# schematic.net
KiCad netlist of a schematic drawn in Altium Designer
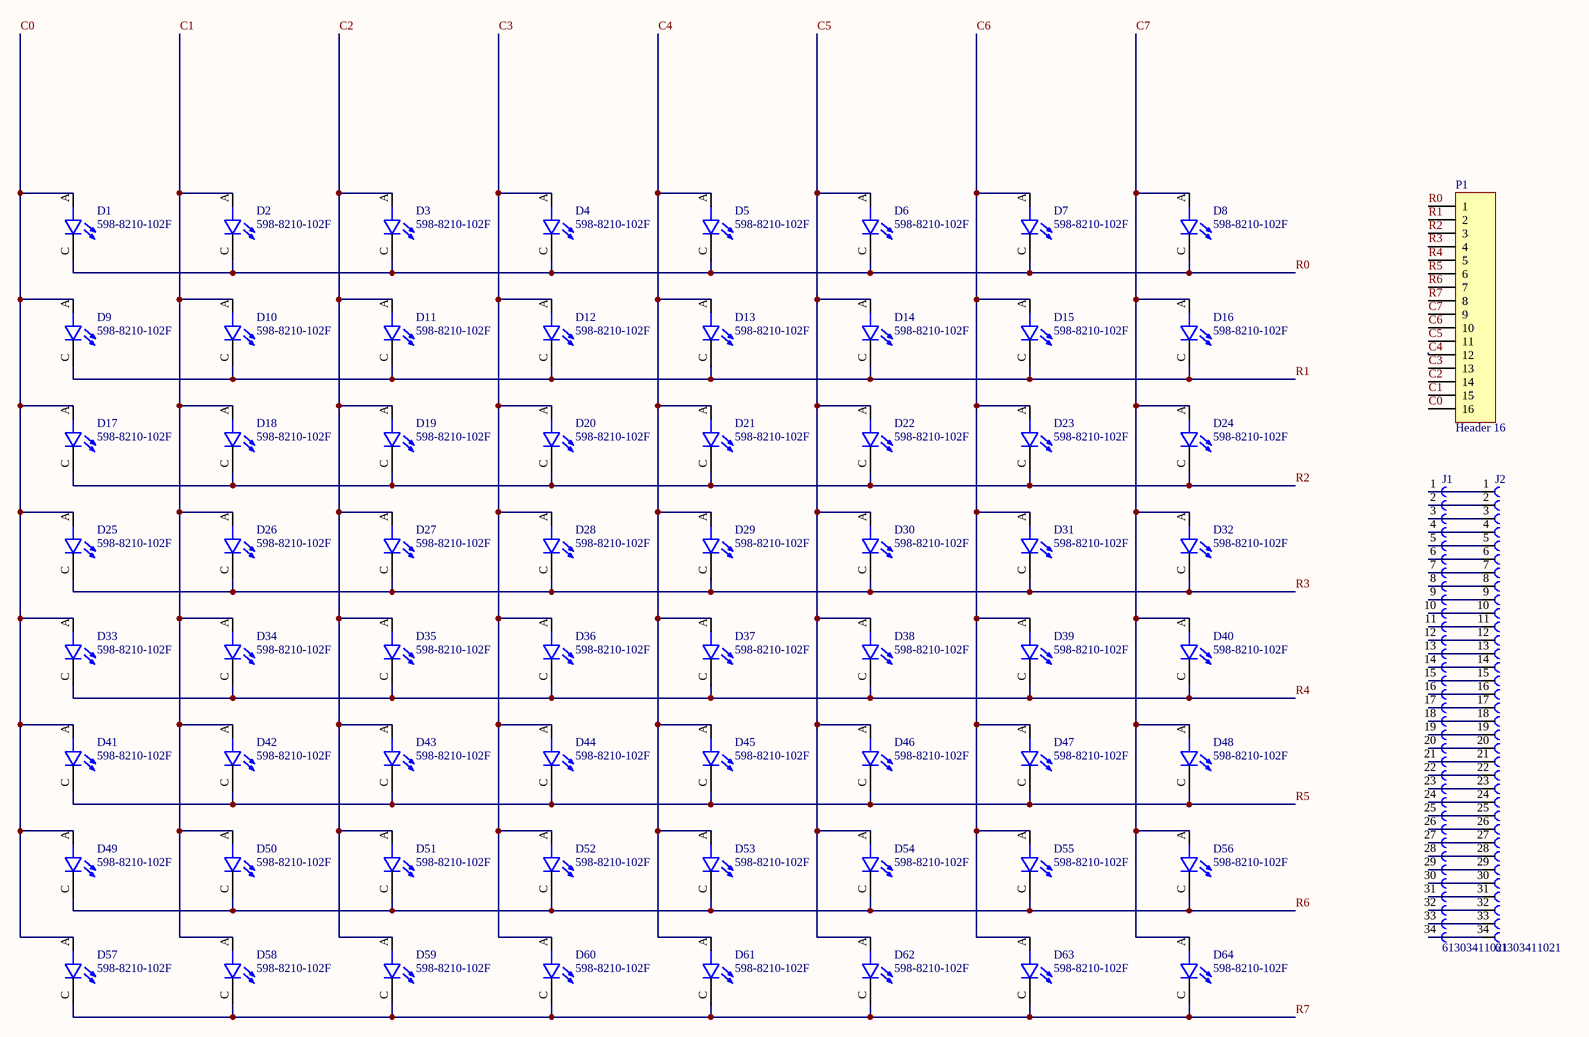
[diagram p0: schematic.SchDoc]

(export (version "E")
  (design (tool "Eeschema 10.0.6"))
  (components
    (comp (ref "D1")
      (value "598-8210-102F")
      (footprint "LEDSC160X320X90-2N")
      (description "Red 635nm LED Indication - Discrete 2V 1206 (3216 Metric)")
      (fields (field (name "MF") "{'manufacturer': u'Dialight'}"))
      (libsource (lib "SnapEDA_Library") (part "598-8210-102F"))
    )
    (comp (ref "D2")
      (value "598-8210-102F")
      (footprint "LEDSC160X320X90-2N")
      (description "Red 635nm LED Indication - Discrete 2V 1206 (3216 Metric)")
      (fields (field (name "MF") "{'manufacturer': u'Dialight'}"))
      (libsource (lib "SnapEDA_Library") (part "598-8210-102F"))
    )
    (comp (ref "D3")
      (value "598-8210-102F")
      (footprint "LEDSC160X320X90-2N")
      (description "Red 635nm LED Indication - Discrete 2V 1206 (3216 Metric)")
      (fields (field (name "MF") "{'manufacturer': u'Dialight'}"))
      (libsource (lib "SnapEDA_Library") (part "598-8210-102F"))
    )
    (comp (ref "D4")
      (value "598-8210-102F")
      (footprint "LEDSC160X320X90-2N")
      (description "Red 635nm LED Indication - Discrete 2V 1206 (3216 Metric)")
      (fields (field (name "MF") "{'manufacturer': u'Dialight'}"))
      (libsource (lib "SnapEDA_Library") (part "598-8210-102F"))
    )
    (comp (ref "D5")
      (value "598-8210-102F")
      (footprint "LEDSC160X320X90-2N")
      (description "Red 635nm LED Indication - Discrete 2V 1206 (3216 Metric)")
      (fields (field (name "MF") "{'manufacturer': u'Dialight'}"))
      (libsource (lib "SnapEDA_Library") (part "598-8210-102F"))
    )
    (comp (ref "D6")
      (value "598-8210-102F")
      (footprint "LEDSC160X320X90-2N")
      (description "Red 635nm LED Indication - Discrete 2V 1206 (3216 Metric)")
      (fields (field (name "MF") "{'manufacturer': u'Dialight'}"))
      (libsource (lib "SnapEDA_Library") (part "598-8210-102F"))
    )
    (comp (ref "D7")
      (value "598-8210-102F")
      (footprint "LEDSC160X320X90-2N")
      (description "Red 635nm LED Indication - Discrete 2V 1206 (3216 Metric)")
      (fields (field (name "MF") "{'manufacturer': u'Dialight'}"))
      (libsource (lib "SnapEDA_Library") (part "598-8210-102F"))
    )
    (comp (ref "D8")
      (value "598-8210-102F")
      (footprint "LEDSC160X320X90-2N")
      (description "Red 635nm LED Indication - Discrete 2V 1206 (3216 Metric)")
      (fields (field (name "MF") "{'manufacturer': u'Dialight'}"))
      (libsource (lib "SnapEDA_Library") (part "598-8210-102F"))
    )
    (comp (ref "D9")
      (value "598-8210-102F")
      (footprint "LEDSC160X320X90-2N")
      (description "Red 635nm LED Indication - Discrete 2V 1206 (3216 Metric)")
      (fields (field (name "MF") "{'manufacturer': u'Dialight'}"))
      (libsource (lib "SnapEDA_Library") (part "598-8210-102F"))
    )
    (comp (ref "D10")
      (value "598-8210-102F")
      (footprint "LEDSC160X320X90-2N")
      (description "Red 635nm LED Indication - Discrete 2V 1206 (3216 Metric)")
      (fields (field (name "MF") "{'manufacturer': u'Dialight'}"))
      (libsource (lib "SnapEDA_Library") (part "598-8210-102F"))
    )
    (comp (ref "D11")
      (value "598-8210-102F")
      (footprint "LEDSC160X320X90-2N")
      (description "Red 635nm LED Indication - Discrete 2V 1206 (3216 Metric)")
      (fields (field (name "MF") "{'manufacturer': u'Dialight'}"))
      (libsource (lib "SnapEDA_Library") (part "598-8210-102F"))
    )
    (comp (ref "D12")
      (value "598-8210-102F")
      (footprint "LEDSC160X320X90-2N")
      (description "Red 635nm LED Indication - Discrete 2V 1206 (3216 Metric)")
      (fields (field (name "MF") "{'manufacturer': u'Dialight'}"))
      (libsource (lib "SnapEDA_Library") (part "598-8210-102F"))
    )
    (comp (ref "D13")
      (value "598-8210-102F")
      (footprint "LEDSC160X320X90-2N")
      (description "Red 635nm LED Indication - Discrete 2V 1206 (3216 Metric)")
      (fields (field (name "MF") "{'manufacturer': u'Dialight'}"))
      (libsource (lib "SnapEDA_Library") (part "598-8210-102F"))
    )
    (comp (ref "D14")
      (value "598-8210-102F")
      (footprint "LEDSC160X320X90-2N")
      (description "Red 635nm LED Indication - Discrete 2V 1206 (3216 Metric)")
      (fields (field (name "MF") "{'manufacturer': u'Dialight'}"))
      (libsource (lib "SnapEDA_Library") (part "598-8210-102F"))
    )
    (comp (ref "D15")
      (value "598-8210-102F")
      (footprint "LEDSC160X320X90-2N")
      (description "Red 635nm LED Indication - Discrete 2V 1206 (3216 Metric)")
      (fields (field (name "MF") "{'manufacturer': u'Dialight'}"))
      (libsource (lib "SnapEDA_Library") (part "598-8210-102F"))
    )
    (comp (ref "D16")
      (value "598-8210-102F")
      (footprint "LEDSC160X320X90-2N")
      (description "Red 635nm LED Indication - Discrete 2V 1206 (3216 Metric)")
      (fields (field (name "MF") "{'manufacturer': u'Dialight'}"))
      (libsource (lib "SnapEDA_Library") (part "598-8210-102F"))
    )
    (comp (ref "D17")
      (value "598-8210-102F")
      (footprint "LEDSC160X320X90-2N")
      (description "Red 635nm LED Indication - Discrete 2V 1206 (3216 Metric)")
      (fields (field (name "MF") "{'manufacturer': u'Dialight'}"))
      (libsource (lib "SnapEDA_Library") (part "598-8210-102F"))
    )
    (comp (ref "D18")
      (value "598-8210-102F")
      (footprint "LEDSC160X320X90-2N")
      (description "Red 635nm LED Indication - Discrete 2V 1206 (3216 Metric)")
      (fields (field (name "MF") "{'manufacturer': u'Dialight'}"))
      (libsource (lib "SnapEDA_Library") (part "598-8210-102F"))
    )
    (comp (ref "D19")
      (value "598-8210-102F")
      (footprint "LEDSC160X320X90-2N")
      (description "Red 635nm LED Indication - Discrete 2V 1206 (3216 Metric)")
      (fields (field (name "MF") "{'manufacturer': u'Dialight'}"))
      (libsource (lib "SnapEDA_Library") (part "598-8210-102F"))
    )
    (comp (ref "D20")
      (value "598-8210-102F")
      (footprint "LEDSC160X320X90-2N")
      (description "Red 635nm LED Indication - Discrete 2V 1206 (3216 Metric)")
      (fields (field (name "MF") "{'manufacturer': u'Dialight'}"))
      (libsource (lib "SnapEDA_Library") (part "598-8210-102F"))
    )
    (comp (ref "D21")
      (value "598-8210-102F")
      (footprint "LEDSC160X320X90-2N")
      (description "Red 635nm LED Indication - Discrete 2V 1206 (3216 Metric)")
      (fields (field (name "MF") "{'manufacturer': u'Dialight'}"))
      (libsource (lib "SnapEDA_Library") (part "598-8210-102F"))
    )
    (comp (ref "D22")
      (value "598-8210-102F")
      (footprint "LEDSC160X320X90-2N")
      (description "Red 635nm LED Indication - Discrete 2V 1206 (3216 Metric)")
      (fields (field (name "MF") "{'manufacturer': u'Dialight'}"))
      (libsource (lib "SnapEDA_Library") (part "598-8210-102F"))
    )
    (comp (ref "D23")
      (value "598-8210-102F")
      (footprint "LEDSC160X320X90-2N")
      (description "Red 635nm LED Indication - Discrete 2V 1206 (3216 Metric)")
      (fields (field (name "MF") "{'manufacturer': u'Dialight'}"))
      (libsource (lib "SnapEDA_Library") (part "598-8210-102F"))
    )
    (comp (ref "D24")
      (value "598-8210-102F")
      (footprint "LEDSC160X320X90-2N")
      (description "Red 635nm LED Indication - Discrete 2V 1206 (3216 Metric)")
      (fields (field (name "MF") "{'manufacturer': u'Dialight'}"))
      (libsource (lib "SnapEDA_Library") (part "598-8210-102F"))
    )
    (comp (ref "D25")
      (value "598-8210-102F")
      (footprint "LEDSC160X320X90-2N")
      (description "Red 635nm LED Indication - Discrete 2V 1206 (3216 Metric)")
      (fields (field (name "MF") "{'manufacturer': u'Dialight'}"))
      (libsource (lib "SnapEDA_Library") (part "598-8210-102F"))
    )
    (comp (ref "D26")
      (value "598-8210-102F")
      (footprint "LEDSC160X320X90-2N")
      (description "Red 635nm LED Indication - Discrete 2V 1206 (3216 Metric)")
      (fields (field (name "MF") "{'manufacturer': u'Dialight'}"))
      (libsource (lib "SnapEDA_Library") (part "598-8210-102F"))
    )
    (comp (ref "D27")
      (value "598-8210-102F")
      (footprint "LEDSC160X320X90-2N")
      (description "Red 635nm LED Indication - Discrete 2V 1206 (3216 Metric)")
      (fields (field (name "MF") "{'manufacturer': u'Dialight'}"))
      (libsource (lib "SnapEDA_Library") (part "598-8210-102F"))
    )
    (comp (ref "D28")
      (value "598-8210-102F")
      (footprint "LEDSC160X320X90-2N")
      (description "Red 635nm LED Indication - Discrete 2V 1206 (3216 Metric)")
      (fields (field (name "MF") "{'manufacturer': u'Dialight'}"))
      (libsource (lib "SnapEDA_Library") (part "598-8210-102F"))
    )
    (comp (ref "D29")
      (value "598-8210-102F")
      (footprint "LEDSC160X320X90-2N")
      (description "Red 635nm LED Indication - Discrete 2V 1206 (3216 Metric)")
      (fields (field (name "MF") "{'manufacturer': u'Dialight'}"))
      (libsource (lib "SnapEDA_Library") (part "598-8210-102F"))
    )
    (comp (ref "D30")
      (value "598-8210-102F")
      (footprint "LEDSC160X320X90-2N")
      (description "Red 635nm LED Indication - Discrete 2V 1206 (3216 Metric)")
      (fields (field (name "MF") "{'manufacturer': u'Dialight'}"))
      (libsource (lib "SnapEDA_Library") (part "598-8210-102F"))
    )
    (comp (ref "D31")
      (value "598-8210-102F")
      (footprint "LEDSC160X320X90-2N")
      (description "Red 635nm LED Indication - Discrete 2V 1206 (3216 Metric)")
      (fields (field (name "MF") "{'manufacturer': u'Dialight'}"))
      (libsource (lib "SnapEDA_Library") (part "598-8210-102F"))
    )
    (comp (ref "D32")
      (value "598-8210-102F")
      (footprint "LEDSC160X320X90-2N")
      (description "Red 635nm LED Indication - Discrete 2V 1206 (3216 Metric)")
      (fields (field (name "MF") "{'manufacturer': u'Dialight'}"))
      (libsource (lib "SnapEDA_Library") (part "598-8210-102F"))
    )
    (comp (ref "D33")
      (value "598-8210-102F")
      (footprint "LEDSC160X320X90-2N")
      (description "Red 635nm LED Indication - Discrete 2V 1206 (3216 Metric)")
      (fields (field (name "MF") "{'manufacturer': u'Dialight'}"))
      (libsource (lib "SnapEDA_Library") (part "598-8210-102F"))
    )
    (comp (ref "D34")
      (value "598-8210-102F")
      (footprint "LEDSC160X320X90-2N")
      (description "Red 635nm LED Indication - Discrete 2V 1206 (3216 Metric)")
      (fields (field (name "MF") "{'manufacturer': u'Dialight'}"))
      (libsource (lib "SnapEDA_Library") (part "598-8210-102F"))
    )
    (comp (ref "D35")
      (value "598-8210-102F")
      (footprint "LEDSC160X320X90-2N")
      (description "Red 635nm LED Indication - Discrete 2V 1206 (3216 Metric)")
      (fields (field (name "MF") "{'manufacturer': u'Dialight'}"))
      (libsource (lib "SnapEDA_Library") (part "598-8210-102F"))
    )
    (comp (ref "D36")
      (value "598-8210-102F")
      (footprint "LEDSC160X320X90-2N")
      (description "Red 635nm LED Indication - Discrete 2V 1206 (3216 Metric)")
      (fields (field (name "MF") "{'manufacturer': u'Dialight'}"))
      (libsource (lib "SnapEDA_Library") (part "598-8210-102F"))
    )
    (comp (ref "D37")
      (value "598-8210-102F")
      (footprint "LEDSC160X320X90-2N")
      (description "Red 635nm LED Indication - Discrete 2V 1206 (3216 Metric)")
      (fields (field (name "MF") "{'manufacturer': u'Dialight'}"))
      (libsource (lib "SnapEDA_Library") (part "598-8210-102F"))
    )
    (comp (ref "D38")
      (value "598-8210-102F")
      (footprint "LEDSC160X320X90-2N")
      (description "Red 635nm LED Indication - Discrete 2V 1206 (3216 Metric)")
      (fields (field (name "MF") "{'manufacturer': u'Dialight'}"))
      (libsource (lib "SnapEDA_Library") (part "598-8210-102F"))
    )
    (comp (ref "D39")
      (value "598-8210-102F")
      (footprint "LEDSC160X320X90-2N")
      (description "Red 635nm LED Indication - Discrete 2V 1206 (3216 Metric)")
      (fields (field (name "MF") "{'manufacturer': u'Dialight'}"))
      (libsource (lib "SnapEDA_Library") (part "598-8210-102F"))
    )
    (comp (ref "D40")
      (value "598-8210-102F")
      (footprint "LEDSC160X320X90-2N")
      (description "Red 635nm LED Indication - Discrete 2V 1206 (3216 Metric)")
      (fields (field (name "MF") "{'manufacturer': u'Dialight'}"))
      (libsource (lib "SnapEDA_Library") (part "598-8210-102F"))
    )
    (comp (ref "D41")
      (value "598-8210-102F")
      (footprint "LEDSC160X320X90-2N")
      (description "Red 635nm LED Indication - Discrete 2V 1206 (3216 Metric)")
      (fields (field (name "MF") "{'manufacturer': u'Dialight'}"))
      (libsource (lib "SnapEDA_Library") (part "598-8210-102F"))
    )
    (comp (ref "D42")
      (value "598-8210-102F")
      (footprint "LEDSC160X320X90-2N")
      (description "Red 635nm LED Indication - Discrete 2V 1206 (3216 Metric)")
      (fields (field (name "MF") "{'manufacturer': u'Dialight'}"))
      (libsource (lib "SnapEDA_Library") (part "598-8210-102F"))
    )
    (comp (ref "D43")
      (value "598-8210-102F")
      (footprint "LEDSC160X320X90-2N")
      (description "Red 635nm LED Indication - Discrete 2V 1206 (3216 Metric)")
      (fields (field (name "MF") "{'manufacturer': u'Dialight'}"))
      (libsource (lib "SnapEDA_Library") (part "598-8210-102F"))
    )
    (comp (ref "D44")
      (value "598-8210-102F")
      (footprint "LEDSC160X320X90-2N")
      (description "Red 635nm LED Indication - Discrete 2V 1206 (3216 Metric)")
      (fields (field (name "MF") "{'manufacturer': u'Dialight'}"))
      (libsource (lib "SnapEDA_Library") (part "598-8210-102F"))
    )
    (comp (ref "D45")
      (value "598-8210-102F")
      (footprint "LEDSC160X320X90-2N")
      (description "Red 635nm LED Indication - Discrete 2V 1206 (3216 Metric)")
      (fields (field (name "MF") "{'manufacturer': u'Dialight'}"))
      (libsource (lib "SnapEDA_Library") (part "598-8210-102F"))
    )
    (comp (ref "D46")
      (value "598-8210-102F")
      (footprint "LEDSC160X320X90-2N")
      (description "Red 635nm LED Indication - Discrete 2V 1206 (3216 Metric)")
      (fields (field (name "MF") "{'manufacturer': u'Dialight'}"))
      (libsource (lib "SnapEDA_Library") (part "598-8210-102F"))
    )
    (comp (ref "D47")
      (value "598-8210-102F")
      (footprint "LEDSC160X320X90-2N")
      (description "Red 635nm LED Indication - Discrete 2V 1206 (3216 Metric)")
      (fields (field (name "MF") "{'manufacturer': u'Dialight'}"))
      (libsource (lib "SnapEDA_Library") (part "598-8210-102F"))
    )
    (comp (ref "D48")
      (value "598-8210-102F")
      (footprint "LEDSC160X320X90-2N")
      (description "Red 635nm LED Indication - Discrete 2V 1206 (3216 Metric)")
      (fields (field (name "MF") "{'manufacturer': u'Dialight'}"))
      (libsource (lib "SnapEDA_Library") (part "598-8210-102F"))
    )
    (comp (ref "D49")
      (value "598-8210-102F")
      (footprint "LEDSC160X320X90-2N")
      (description "Red 635nm LED Indication - Discrete 2V 1206 (3216 Metric)")
      (fields (field (name "MF") "{'manufacturer': u'Dialight'}"))
      (libsource (lib "SnapEDA_Library") (part "598-8210-102F"))
    )
    (comp (ref "D50")
      (value "598-8210-102F")
      (footprint "LEDSC160X320X90-2N")
      (description "Red 635nm LED Indication - Discrete 2V 1206 (3216 Metric)")
      (fields (field (name "MF") "{'manufacturer': u'Dialight'}"))
      (libsource (lib "SnapEDA_Library") (part "598-8210-102F"))
    )
    (comp (ref "D51")
      (value "598-8210-102F")
      (footprint "LEDSC160X320X90-2N")
      (description "Red 635nm LED Indication - Discrete 2V 1206 (3216 Metric)")
      (fields (field (name "MF") "{'manufacturer': u'Dialight'}"))
      (libsource (lib "SnapEDA_Library") (part "598-8210-102F"))
    )
    (comp (ref "D52")
      (value "598-8210-102F")
      (footprint "LEDSC160X320X90-2N")
      (description "Red 635nm LED Indication - Discrete 2V 1206 (3216 Metric)")
      (fields (field (name "MF") "{'manufacturer': u'Dialight'}"))
      (libsource (lib "SnapEDA_Library") (part "598-8210-102F"))
    )
    (comp (ref "D53")
      (value "598-8210-102F")
      (footprint "LEDSC160X320X90-2N")
      (description "Red 635nm LED Indication - Discrete 2V 1206 (3216 Metric)")
      (fields (field (name "MF") "{'manufacturer': u'Dialight'}"))
      (libsource (lib "SnapEDA_Library") (part "598-8210-102F"))
    )
    (comp (ref "D54")
      (value "598-8210-102F")
      (footprint "LEDSC160X320X90-2N")
      (description "Red 635nm LED Indication - Discrete 2V 1206 (3216 Metric)")
      (fields (field (name "MF") "{'manufacturer': u'Dialight'}"))
      (libsource (lib "SnapEDA_Library") (part "598-8210-102F"))
    )
    (comp (ref "D55")
      (value "598-8210-102F")
      (footprint "LEDSC160X320X90-2N")
      (description "Red 635nm LED Indication - Discrete 2V 1206 (3216 Metric)")
      (fields (field (name "MF") "{'manufacturer': u'Dialight'}"))
      (libsource (lib "SnapEDA_Library") (part "598-8210-102F"))
    )
    (comp (ref "D56")
      (value "598-8210-102F")
      (footprint "LEDSC160X320X90-2N")
      (description "Red 635nm LED Indication - Discrete 2V 1206 (3216 Metric)")
      (fields (field (name "MF") "{'manufacturer': u'Dialight'}"))
      (libsource (lib "SnapEDA_Library") (part "598-8210-102F"))
    )
    (comp (ref "D57")
      (value "598-8210-102F")
      (footprint "LEDSC160X320X90-2N")
      (description "Red 635nm LED Indication - Discrete 2V 1206 (3216 Metric)")
      (fields (field (name "MF") "{'manufacturer': u'Dialight'}"))
      (libsource (lib "SnapEDA_Library") (part "598-8210-102F"))
    )
    (comp (ref "D58")
      (value "598-8210-102F")
      (footprint "LEDSC160X320X90-2N")
      (description "Red 635nm LED Indication - Discrete 2V 1206 (3216 Metric)")
      (fields (field (name "MF") "{'manufacturer': u'Dialight'}"))
      (libsource (lib "SnapEDA_Library") (part "598-8210-102F"))
    )
    (comp (ref "D59")
      (value "598-8210-102F")
      (footprint "LEDSC160X320X90-2N")
      (description "Red 635nm LED Indication - Discrete 2V 1206 (3216 Metric)")
      (fields (field (name "MF") "{'manufacturer': u'Dialight'}"))
      (libsource (lib "SnapEDA_Library") (part "598-8210-102F"))
    )
    (comp (ref "D60")
      (value "598-8210-102F")
      (footprint "LEDSC160X320X90-2N")
      (description "Red 635nm LED Indication - Discrete 2V 1206 (3216 Metric)")
      (fields (field (name "MF") "{'manufacturer': u'Dialight'}"))
      (libsource (lib "SnapEDA_Library") (part "598-8210-102F"))
    )
    (comp (ref "D61")
      (value "598-8210-102F")
      (footprint "LEDSC160X320X90-2N")
      (description "Red 635nm LED Indication - Discrete 2V 1206 (3216 Metric)")
      (fields (field (name "MF") "{'manufacturer': u'Dialight'}"))
      (libsource (lib "SnapEDA_Library") (part "598-8210-102F"))
    )
    (comp (ref "D62")
      (value "598-8210-102F")
      (footprint "LEDSC160X320X90-2N")
      (description "Red 635nm LED Indication - Discrete 2V 1206 (3216 Metric)")
      (fields (field (name "MF") "{'manufacturer': u'Dialight'}"))
      (libsource (lib "SnapEDA_Library") (part "598-8210-102F"))
    )
    (comp (ref "D63")
      (value "598-8210-102F")
      (footprint "LEDSC160X320X90-2N")
      (description "Red 635nm LED Indication - Discrete 2V 1206 (3216 Metric)")
      (fields (field (name "MF") "{'manufacturer': u'Dialight'}"))
      (libsource (lib "SnapEDA_Library") (part "598-8210-102F"))
    )
    (comp (ref "D64")
      (value "598-8210-102F")
      (footprint "LEDSC160X320X90-2N")
      (description "Red 635nm LED Indication - Discrete 2V 1206 (3216 Metric)")
      (fields (field (name "MF") "{'manufacturer': u'Dialight'}"))
      (libsource (lib "SnapEDA_Library") (part "598-8210-102F"))
    )
    (comp (ref "J1")
      (value "61303411021")
      (footprint "61303411021:61303411021")
      (fields (field (name "MF") "{'manufacturer': u'~{W}xfcrth Elektronik'}"))
      (libsource (lib "61303411021") (part "61303411021"))
    )
    (comp (ref "J2")
      (value "61303411021")
      (footprint "61303411021:61303411021")
      (fields (field (name "MF") "{'manufacturer': u'~{W}xfcrth Elektronik'}"))
      (libsource (lib "61303411021") (part "61303411021"))
    )
    (comp (ref "P1")
      (value "Header 16")
      (footprint "HDR1X16")
      (description "Header, 16-Pin")
      (fields (field (name "PUBLISHER") "Altium Limited"))
      (libsource (lib "Miscellaneous Connectors") (part "Header 16"))
    )
  )
  (nets
    (net (code "1") (name "/C0") (class "Default")
      (node (ref "D1") (pin "A") (pinfunction "A_A") (pintype "passive"))
      (node (ref "D17") (pin "A") (pinfunction "A_A") (pintype "passive"))
      (node (ref "D25") (pin "A") (pinfunction "A_A") (pintype "passive"))
      (node (ref "D33") (pin "A") (pinfunction "A_A") (pintype "passive"))
      (node (ref "D41") (pin "A") (pinfunction "A_A") (pintype "passive"))
      (node (ref "D49") (pin "A") (pinfunction "A_A") (pintype "passive"))
      (node (ref "D57") (pin "A") (pinfunction "A_A") (pintype "passive"))
      (node (ref "D9") (pin "A") (pinfunction "A_A") (pintype "passive"))
      (node (ref "P1") (pin "16") (pinfunction "16_16") (pintype "passive"))
    )
    (net (code "2") (name "/C1") (class "Default")
      (node (ref "D10") (pin "A") (pinfunction "A_A") (pintype "passive"))
      (node (ref "D18") (pin "A") (pinfunction "A_A") (pintype "passive"))
      (node (ref "D2") (pin "A") (pinfunction "A_A") (pintype "passive"))
      (node (ref "D26") (pin "A") (pinfunction "A_A") (pintype "passive"))
      (node (ref "D34") (pin "A") (pinfunction "A_A") (pintype "passive"))
      (node (ref "D42") (pin "A") (pinfunction "A_A") (pintype "passive"))
      (node (ref "D50") (pin "A") (pinfunction "A_A") (pintype "passive"))
      (node (ref "D58") (pin "A") (pinfunction "A_A") (pintype "passive"))
      (node (ref "P1") (pin "15") (pinfunction "15_15") (pintype "passive"))
    )
    (net (code "3") (name "/C2") (class "Default")
      (node (ref "D11") (pin "A") (pinfunction "A_A") (pintype "passive"))
      (node (ref "D19") (pin "A") (pinfunction "A_A") (pintype "passive"))
      (node (ref "D27") (pin "A") (pinfunction "A_A") (pintype "passive"))
      (node (ref "D3") (pin "A") (pinfunction "A_A") (pintype "passive"))
      (node (ref "D35") (pin "A") (pinfunction "A_A") (pintype "passive"))
      (node (ref "D43") (pin "A") (pinfunction "A_A") (pintype "passive"))
      (node (ref "D51") (pin "A") (pinfunction "A_A") (pintype "passive"))
      (node (ref "D59") (pin "A") (pinfunction "A_A") (pintype "passive"))
      (node (ref "P1") (pin "14") (pinfunction "14_14") (pintype "passive"))
    )
    (net (code "4") (name "/C3") (class "Default")
      (node (ref "D12") (pin "A") (pinfunction "A_A") (pintype "passive"))
      (node (ref "D20") (pin "A") (pinfunction "A_A") (pintype "passive"))
      (node (ref "D28") (pin "A") (pinfunction "A_A") (pintype "passive"))
      (node (ref "D36") (pin "A") (pinfunction "A_A") (pintype "passive"))
      (node (ref "D4") (pin "A") (pinfunction "A_A") (pintype "passive"))
      (node (ref "D44") (pin "A") (pinfunction "A_A") (pintype "passive"))
      (node (ref "D52") (pin "A") (pinfunction "A_A") (pintype "passive"))
      (node (ref "D60") (pin "A") (pinfunction "A_A") (pintype "passive"))
      (node (ref "P1") (pin "13") (pinfunction "13_13") (pintype "passive"))
    )
    (net (code "5") (name "/C4") (class "Default")
      (node (ref "D13") (pin "A") (pinfunction "A_A") (pintype "passive"))
      (node (ref "D21") (pin "A") (pinfunction "A_A") (pintype "passive"))
      (node (ref "D29") (pin "A") (pinfunction "A_A") (pintype "passive"))
      (node (ref "D37") (pin "A") (pinfunction "A_A") (pintype "passive"))
      (node (ref "D45") (pin "A") (pinfunction "A_A") (pintype "passive"))
      (node (ref "D5") (pin "A") (pinfunction "A_A") (pintype "passive"))
      (node (ref "D53") (pin "A") (pinfunction "A_A") (pintype "passive"))
      (node (ref "D61") (pin "A") (pinfunction "A_A") (pintype "passive"))
      (node (ref "P1") (pin "12") (pinfunction "12_12") (pintype "passive"))
    )
    (net (code "6") (name "/C5") (class "Default")
      (node (ref "D14") (pin "A") (pinfunction "A_A") (pintype "passive"))
      (node (ref "D22") (pin "A") (pinfunction "A_A") (pintype "passive"))
      (node (ref "D30") (pin "A") (pinfunction "A_A") (pintype "passive"))
      (node (ref "D38") (pin "A") (pinfunction "A_A") (pintype "passive"))
      (node (ref "D46") (pin "A") (pinfunction "A_A") (pintype "passive"))
      (node (ref "D54") (pin "A") (pinfunction "A_A") (pintype "passive"))
      (node (ref "D6") (pin "A") (pinfunction "A_A") (pintype "passive"))
      (node (ref "D62") (pin "A") (pinfunction "A_A") (pintype "passive"))
      (node (ref "P1") (pin "11") (pinfunction "11_11") (pintype "passive"))
    )
    (net (code "7") (name "/C6") (class "Default")
      (node (ref "D15") (pin "A") (pinfunction "A_A") (pintype "passive"))
      (node (ref "D23") (pin "A") (pinfunction "A_A") (pintype "passive"))
      (node (ref "D31") (pin "A") (pinfunction "A_A") (pintype "passive"))
      (node (ref "D39") (pin "A") (pinfunction "A_A") (pintype "passive"))
      (node (ref "D47") (pin "A") (pinfunction "A_A") (pintype "passive"))
      (node (ref "D55") (pin "A") (pinfunction "A_A") (pintype "passive"))
      (node (ref "D63") (pin "A") (pinfunction "A_A") (pintype "passive"))
      (node (ref "D7") (pin "A") (pinfunction "A_A") (pintype "passive"))
      (node (ref "P1") (pin "10") (pinfunction "10_10") (pintype "passive"))
    )
    (net (code "8") (name "/C7") (class "Default")
      (node (ref "D16") (pin "A") (pinfunction "A_A") (pintype "passive"))
      (node (ref "D24") (pin "A") (pinfunction "A_A") (pintype "passive"))
      (node (ref "D32") (pin "A") (pinfunction "A_A") (pintype "passive"))
      (node (ref "D40") (pin "A") (pinfunction "A_A") (pintype "passive"))
      (node (ref "D48") (pin "A") (pinfunction "A_A") (pintype "passive"))
      (node (ref "D56") (pin "A") (pinfunction "A_A") (pintype "passive"))
      (node (ref "D64") (pin "A") (pinfunction "A_A") (pintype "passive"))
      (node (ref "D8") (pin "A") (pinfunction "A_A") (pintype "passive"))
      (node (ref "P1") (pin "9") (pinfunction "9_9") (pintype "passive"))
    )
    (net (code "9") (name "/R0") (class "Default")
      (node (ref "D1") (pin "C") (pinfunction "C_C") (pintype "passive"))
      (node (ref "D2") (pin "C") (pinfunction "C_C") (pintype "passive"))
      (node (ref "D3") (pin "C") (pinfunction "C_C") (pintype "passive"))
      (node (ref "D4") (pin "C") (pinfunction "C_C") (pintype "passive"))
      (node (ref "D5") (pin "C") (pinfunction "C_C") (pintype "passive"))
      (node (ref "D6") (pin "C") (pinfunction "C_C") (pintype "passive"))
      (node (ref "D7") (pin "C") (pinfunction "C_C") (pintype "passive"))
      (node (ref "D8") (pin "C") (pinfunction "C_C") (pintype "passive"))
      (node (ref "P1") (pin "1") (pinfunction "1_1") (pintype "passive"))
    )
    (net (code "10") (name "/R1") (class "Default")
      (node (ref "D10") (pin "C") (pinfunction "C_C") (pintype "passive"))
      (node (ref "D11") (pin "C") (pinfunction "C_C") (pintype "passive"))
      (node (ref "D12") (pin "C") (pinfunction "C_C") (pintype "passive"))
      (node (ref "D13") (pin "C") (pinfunction "C_C") (pintype "passive"))
      (node (ref "D14") (pin "C") (pinfunction "C_C") (pintype "passive"))
      (node (ref "D15") (pin "C") (pinfunction "C_C") (pintype "passive"))
      (node (ref "D16") (pin "C") (pinfunction "C_C") (pintype "passive"))
      (node (ref "D9") (pin "C") (pinfunction "C_C") (pintype "passive"))
      (node (ref "P1") (pin "2") (pinfunction "2_2") (pintype "passive"))
    )
    (net (code "11") (name "/R2") (class "Default")
      (node (ref "D17") (pin "C") (pinfunction "C_C") (pintype "passive"))
      (node (ref "D18") (pin "C") (pinfunction "C_C") (pintype "passive"))
      (node (ref "D19") (pin "C") (pinfunction "C_C") (pintype "passive"))
      (node (ref "D20") (pin "C") (pinfunction "C_C") (pintype "passive"))
      (node (ref "D21") (pin "C") (pinfunction "C_C") (pintype "passive"))
      (node (ref "D22") (pin "C") (pinfunction "C_C") (pintype "passive"))
      (node (ref "D23") (pin "C") (pinfunction "C_C") (pintype "passive"))
      (node (ref "D24") (pin "C") (pinfunction "C_C") (pintype "passive"))
      (node (ref "P1") (pin "3") (pinfunction "3_3") (pintype "passive"))
    )
    (net (code "12") (name "/R3") (class "Default")
      (node (ref "D25") (pin "C") (pinfunction "C_C") (pintype "passive"))
      (node (ref "D26") (pin "C") (pinfunction "C_C") (pintype "passive"))
      (node (ref "D27") (pin "C") (pinfunction "C_C") (pintype "passive"))
      (node (ref "D28") (pin "C") (pinfunction "C_C") (pintype "passive"))
      (node (ref "D29") (pin "C") (pinfunction "C_C") (pintype "passive"))
      (node (ref "D30") (pin "C") (pinfunction "C_C") (pintype "passive"))
      (node (ref "D31") (pin "C") (pinfunction "C_C") (pintype "passive"))
      (node (ref "D32") (pin "C") (pinfunction "C_C") (pintype "passive"))
      (node (ref "P1") (pin "4") (pinfunction "4_4") (pintype "passive"))
    )
    (net (code "13") (name "/R4") (class "Default")
      (node (ref "D33") (pin "C") (pinfunction "C_C") (pintype "passive"))
      (node (ref "D34") (pin "C") (pinfunction "C_C") (pintype "passive"))
      (node (ref "D35") (pin "C") (pinfunction "C_C") (pintype "passive"))
      (node (ref "D36") (pin "C") (pinfunction "C_C") (pintype "passive"))
      (node (ref "D37") (pin "C") (pinfunction "C_C") (pintype "passive"))
      (node (ref "D38") (pin "C") (pinfunction "C_C") (pintype "passive"))
      (node (ref "D39") (pin "C") (pinfunction "C_C") (pintype "passive"))
      (node (ref "D40") (pin "C") (pinfunction "C_C") (pintype "passive"))
      (node (ref "P1") (pin "5") (pinfunction "5_5") (pintype "passive"))
    )
    (net (code "14") (name "/R5") (class "Default")
      (node (ref "D41") (pin "C") (pinfunction "C_C") (pintype "passive"))
      (node (ref "D42") (pin "C") (pinfunction "C_C") (pintype "passive"))
      (node (ref "D43") (pin "C") (pinfunction "C_C") (pintype "passive"))
      (node (ref "D44") (pin "C") (pinfunction "C_C") (pintype "passive"))
      (node (ref "D45") (pin "C") (pinfunction "C_C") (pintype "passive"))
      (node (ref "D46") (pin "C") (pinfunction "C_C") (pintype "passive"))
      (node (ref "D47") (pin "C") (pinfunction "C_C") (pintype "passive"))
      (node (ref "D48") (pin "C") (pinfunction "C_C") (pintype "passive"))
      (node (ref "P1") (pin "6") (pinfunction "6_6") (pintype "passive"))
    )
    (net (code "15") (name "/R6") (class "Default")
      (node (ref "D49") (pin "C") (pinfunction "C_C") (pintype "passive"))
      (node (ref "D50") (pin "C") (pinfunction "C_C") (pintype "passive"))
      (node (ref "D51") (pin "C") (pinfunction "C_C") (pintype "passive"))
      (node (ref "D52") (pin "C") (pinfunction "C_C") (pintype "passive"))
      (node (ref "D53") (pin "C") (pinfunction "C_C") (pintype "passive"))
      (node (ref "D54") (pin "C") (pinfunction "C_C") (pintype "passive"))
      (node (ref "D55") (pin "C") (pinfunction "C_C") (pintype "passive"))
      (node (ref "D56") (pin "C") (pinfunction "C_C") (pintype "passive"))
      (node (ref "P1") (pin "7") (pinfunction "7_7") (pintype "passive"))
    )
    (net (code "16") (name "/R7") (class "Default")
      (node (ref "D57") (pin "C") (pinfunction "C_C") (pintype "passive"))
      (node (ref "D58") (pin "C") (pinfunction "C_C") (pintype "passive"))
      (node (ref "D59") (pin "C") (pinfunction "C_C") (pintype "passive"))
      (node (ref "D60") (pin "C") (pinfunction "C_C") (pintype "passive"))
      (node (ref "D61") (pin "C") (pinfunction "C_C") (pintype "passive"))
      (node (ref "D62") (pin "C") (pinfunction "C_C") (pintype "passive"))
      (node (ref "D63") (pin "C") (pinfunction "C_C") (pintype "passive"))
      (node (ref "D64") (pin "C") (pinfunction "C_C") (pintype "passive"))
      (node (ref "P1") (pin "8") (pinfunction "8_8") (pintype "passive"))
    )
    (net (code "17") (name "Net-(J1-Pad1)") (class "Default")
      (node (ref "J1") (pin "1") (pinfunction "1_1") (pintype "passive"))
      (node (ref "J2") (pin "1") (pinfunction "1_1") (pintype "passive"))
    )
    (net (code "18") (name "Net-(J1-Pad2)") (class "Default")
      (node (ref "J1") (pin "2") (pinfunction "2_2") (pintype "passive"))
      (node (ref "J2") (pin "2") (pinfunction "2_2") (pintype "passive"))
    )
    (net (code "19") (name "Net-(J1-Pad3)") (class "Default")
      (node (ref "J1") (pin "3") (pinfunction "3_3") (pintype "passive"))
      (node (ref "J2") (pin "3") (pinfunction "3_3") (pintype "passive"))
    )
    (net (code "20") (name "Net-(J1-Pad4)") (class "Default")
      (node (ref "J1") (pin "4") (pinfunction "4_4") (pintype "passive"))
      (node (ref "J2") (pin "4") (pinfunction "4_4") (pintype "passive"))
    )
    (net (code "21") (name "Net-(J1-Pad5)") (class "Default")
      (node (ref "J1") (pin "5") (pinfunction "5_5") (pintype "passive"))
      (node (ref "J2") (pin "5") (pinfunction "5_5") (pintype "passive"))
    )
    (net (code "22") (name "Net-(J1-Pad6)") (class "Default")
      (node (ref "J1") (pin "6") (pinfunction "6_6") (pintype "passive"))
      (node (ref "J2") (pin "6") (pinfunction "6_6") (pintype "passive"))
    )
    (net (code "23") (name "Net-(J1-Pad7)") (class "Default")
      (node (ref "J1") (pin "7") (pinfunction "7_7") (pintype "passive"))
      (node (ref "J2") (pin "7") (pinfunction "7_7") (pintype "passive"))
    )
    (net (code "24") (name "Net-(J1-Pad8)") (class "Default")
      (node (ref "J1") (pin "8") (pinfunction "8_8") (pintype "passive"))
      (node (ref "J2") (pin "8") (pinfunction "8_8") (pintype "passive"))
    )
    (net (code "25") (name "Net-(J1-Pad9)") (class "Default")
      (node (ref "J1") (pin "9") (pinfunction "9_9") (pintype "passive"))
      (node (ref "J2") (pin "9") (pinfunction "9_9") (pintype "passive"))
    )
    (net (code "26") (name "Net-(J1-Pad10)") (class "Default")
      (node (ref "J1") (pin "10") (pinfunction "10_10") (pintype "passive"))
      (node (ref "J2") (pin "10") (pinfunction "10_10") (pintype "passive"))
    )
    (net (code "27") (name "Net-(J1-Pad11)") (class "Default")
      (node (ref "J1") (pin "11") (pinfunction "11_11") (pintype "passive"))
      (node (ref "J2") (pin "11") (pinfunction "11_11") (pintype "passive"))
    )
    (net (code "28") (name "Net-(J1-Pad12)") (class "Default")
      (node (ref "J1") (pin "12") (pinfunction "12_12") (pintype "passive"))
      (node (ref "J2") (pin "12") (pinfunction "12_12") (pintype "passive"))
    )
    (net (code "29") (name "Net-(J1-Pad13)") (class "Default")
      (node (ref "J1") (pin "13") (pinfunction "13_13") (pintype "passive"))
      (node (ref "J2") (pin "13") (pinfunction "13_13") (pintype "passive"))
    )
    (net (code "30") (name "Net-(J1-Pad14)") (class "Default")
      (node (ref "J1") (pin "14") (pinfunction "14_14") (pintype "passive"))
      (node (ref "J2") (pin "14") (pinfunction "14_14") (pintype "passive"))
    )
    (net (code "31") (name "Net-(J1-Pad15)") (class "Default")
      (node (ref "J1") (pin "15") (pinfunction "15_15") (pintype "passive"))
      (node (ref "J2") (pin "15") (pinfunction "15_15") (pintype "passive"))
    )
    (net (code "32") (name "Net-(J1-Pad16)") (class "Default")
      (node (ref "J1") (pin "16") (pinfunction "16_16") (pintype "passive"))
      (node (ref "J2") (pin "16") (pinfunction "16_16") (pintype "passive"))
    )
    (net (code "33") (name "Net-(J1-Pad17)") (class "Default")
      (node (ref "J1") (pin "17") (pinfunction "17_17") (pintype "passive"))
      (node (ref "J2") (pin "17") (pinfunction "17_17") (pintype "passive"))
    )
    (net (code "34") (name "Net-(J1-Pad18)") (class "Default")
      (node (ref "J1") (pin "18") (pinfunction "18_18") (pintype "passive"))
      (node (ref "J2") (pin "18") (pinfunction "18_18") (pintype "passive"))
    )
    (net (code "35") (name "Net-(J1-Pad19)") (class "Default")
      (node (ref "J1") (pin "19") (pinfunction "19_19") (pintype "passive"))
      (node (ref "J2") (pin "19") (pinfunction "19_19") (pintype "passive"))
    )
    (net (code "36") (name "Net-(J1-Pad20)") (class "Default")
      (node (ref "J1") (pin "20") (pinfunction "20_20") (pintype "passive"))
      (node (ref "J2") (pin "20") (pinfunction "20_20") (pintype "passive"))
    )
    (net (code "37") (name "Net-(J1-Pad21)") (class "Default")
      (node (ref "J1") (pin "21") (pinfunction "21_21") (pintype "passive"))
      (node (ref "J2") (pin "21") (pinfunction "21_21") (pintype "passive"))
    )
    (net (code "38") (name "Net-(J1-Pad22)") (class "Default")
      (node (ref "J1") (pin "22") (pinfunction "22_22") (pintype "passive"))
      (node (ref "J2") (pin "22") (pinfunction "22_22") (pintype "passive"))
    )
    (net (code "39") (name "Net-(J1-Pad23)") (class "Default")
      (node (ref "J1") (pin "23") (pinfunction "23_23") (pintype "passive"))
      (node (ref "J2") (pin "23") (pinfunction "23_23") (pintype "passive"))
    )
    (net (code "40") (name "Net-(J1-Pad24)") (class "Default")
      (node (ref "J1") (pin "24") (pinfunction "24_24") (pintype "passive"))
      (node (ref "J2") (pin "24") (pinfunction "24_24") (pintype "passive"))
    )
    (net (code "41") (name "Net-(J1-Pad25)") (class "Default")
      (node (ref "J1") (pin "25") (pinfunction "25_25") (pintype "passive"))
      (node (ref "J2") (pin "25") (pinfunction "25_25") (pintype "passive"))
    )
    (net (code "42") (name "Net-(J1-Pad26)") (class "Default")
      (node (ref "J1") (pin "26") (pinfunction "26_26") (pintype "passive"))
      (node (ref "J2") (pin "26") (pinfunction "26_26") (pintype "passive"))
    )
    (net (code "43") (name "Net-(J1-Pad27)") (class "Default")
      (node (ref "J1") (pin "27") (pinfunction "27_27") (pintype "passive"))
      (node (ref "J2") (pin "27") (pinfunction "27_27") (pintype "passive"))
    )
    (net (code "44") (name "Net-(J1-Pad28)") (class "Default")
      (node (ref "J1") (pin "28") (pinfunction "28_28") (pintype "passive"))
      (node (ref "J2") (pin "28") (pinfunction "28_28") (pintype "passive"))
    )
    (net (code "45") (name "Net-(J1-Pad29)") (class "Default")
      (node (ref "J1") (pin "29") (pinfunction "29_29") (pintype "passive"))
      (node (ref "J2") (pin "29") (pinfunction "29_29") (pintype "passive"))
    )
    (net (code "46") (name "Net-(J1-Pad30)") (class "Default")
      (node (ref "J1") (pin "30") (pinfunction "30_30") (pintype "passive"))
      (node (ref "J2") (pin "30") (pinfunction "30_30") (pintype "passive"))
    )
    (net (code "47") (name "Net-(J1-Pad31)") (class "Default")
      (node (ref "J1") (pin "31") (pinfunction "31_31") (pintype "passive"))
      (node (ref "J2") (pin "31") (pinfunction "31_31") (pintype "passive"))
    )
    (net (code "48") (name "Net-(J1-Pad32)") (class "Default")
      (node (ref "J1") (pin "32") (pinfunction "32_32") (pintype "passive"))
      (node (ref "J2") (pin "32") (pinfunction "32_32") (pintype "passive"))
    )
    (net (code "49") (name "Net-(J1-Pad33)") (class "Default")
      (node (ref "J1") (pin "33") (pinfunction "33_33") (pintype "passive"))
      (node (ref "J2") (pin "33") (pinfunction "33_33") (pintype "passive"))
    )
    (net (code "50") (name "Net-(J1-Pad34)") (class "Default")
      (node (ref "J1") (pin "34") (pinfunction "34_34") (pintype "passive"))
      (node (ref "J2") (pin "34") (pinfunction "34_34") (pintype "passive"))
    )
  )
)
